# ADXL.net
KiCad netlist of a schematic drawn in EasyEDA Pro
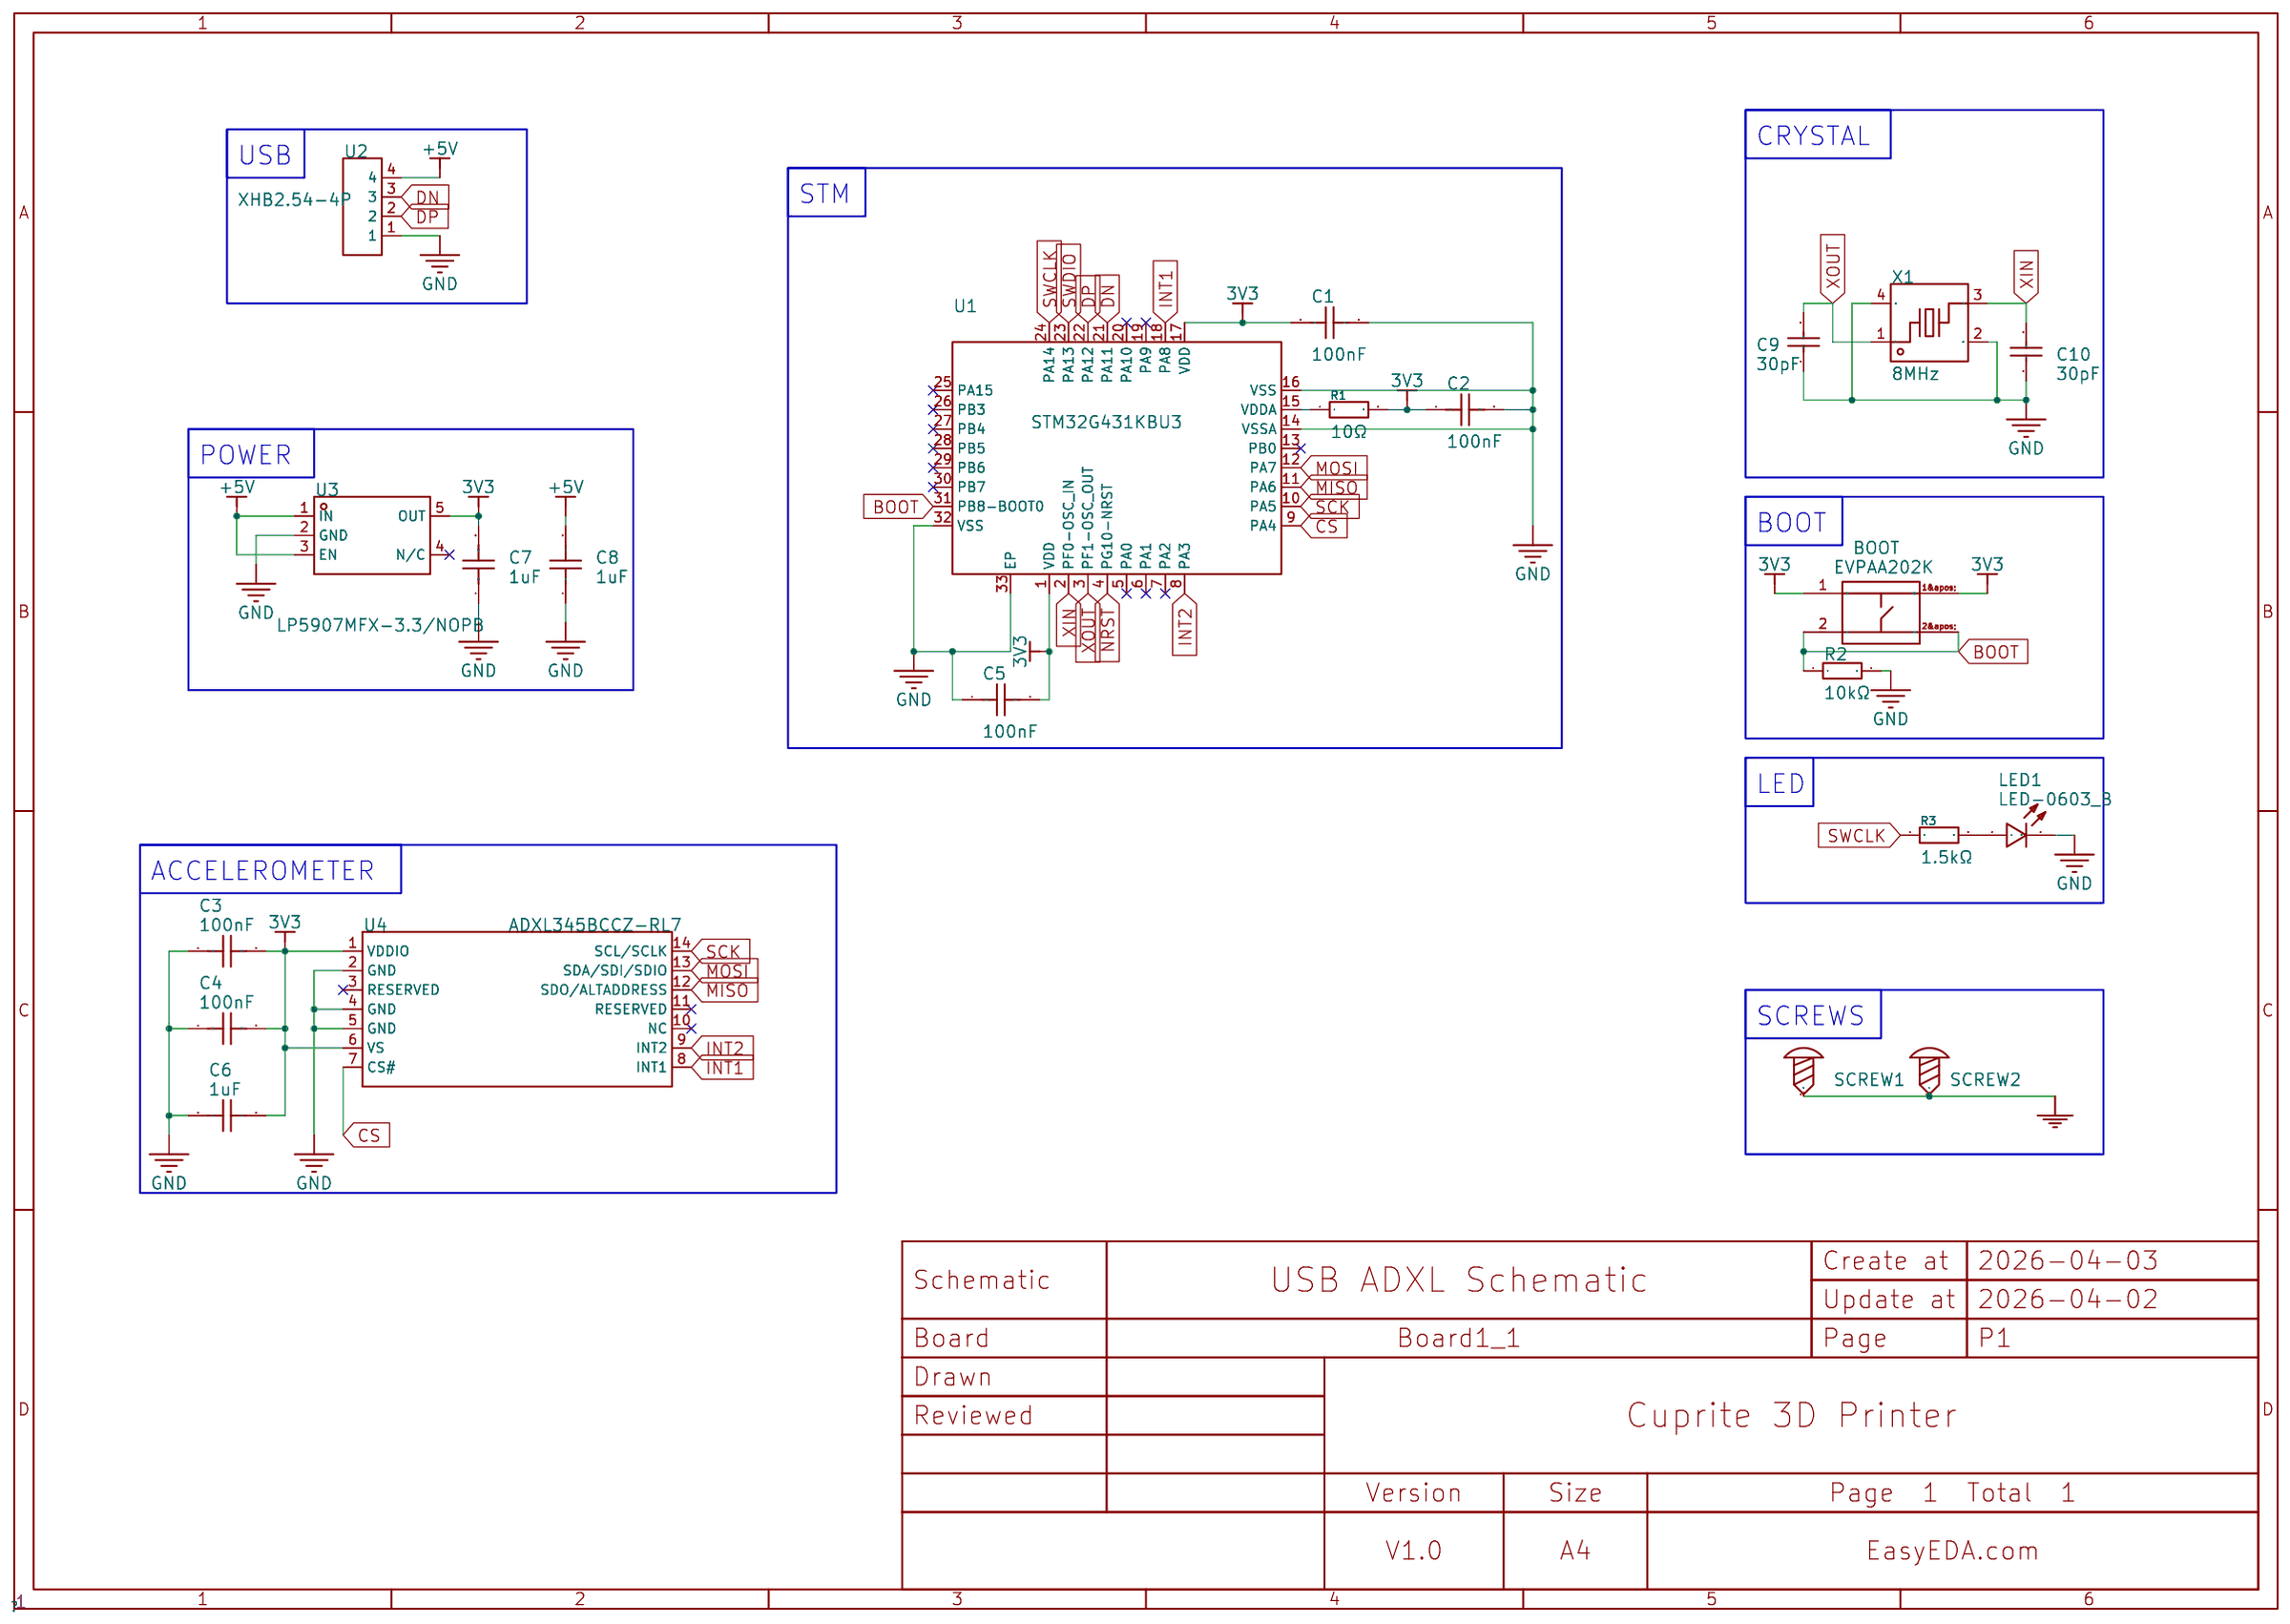
[diagram p0: schematic sheet]

(export (version "E")
  (design (tool "Eeschema 10.0.6"))
  (components
    (comp (ref "BOOT")
      (value "EVPAA202K")
      (footprint "easyedapro:KEY-SMD_4P-L3.5-W2.9-P1.48-LS4.3-TL")
      (fields (field (name "Manufacturer") "PANASONIC(松下)"))
      (libsource (lib "easyedapro") (part "EVPAA202K"))
    )
    (comp (ref "C1")
      (value "100nF")
      (footprint "easyedapro:C0402")
      (fields
        (field (name "Manufacturer Part") "CL05B104KO5NNNC")
        (field (name "Manufacturer") "SAMSUNG(三星)")
      )
      (libsource (lib "easyedapro") (part "CL05B104KO5NNNC"))
    )
    (comp (ref "C2")
      (value "100nF")
      (footprint "easyedapro:C0402")
      (fields
        (field (name "Manufacturer Part") "CL05B104KO5NNNC")
        (field (name "Manufacturer") "SAMSUNG(三星)")
      )
      (libsource (lib "easyedapro") (part "CL05B104KO5NNNC"))
    )
    (comp (ref "C3")
      (value "100nF")
      (footprint "easyedapro:C0402")
      (fields
        (field (name "Manufacturer Part") "CL05B104KO5NNNC")
        (field (name "Manufacturer") "SAMSUNG(三星)")
      )
      (libsource (lib "easyedapro") (part "CL05B104KO5NNNC"))
    )
    (comp (ref "C4")
      (value "100nF")
      (footprint "easyedapro:C0402")
      (fields
        (field (name "Manufacturer Part") "CL05B104KO5NNNC")
        (field (name "Manufacturer") "SAMSUNG(三星)")
      )
      (libsource (lib "easyedapro") (part "CL05B104KO5NNNC"))
    )
    (comp (ref "C5")
      (value "100nF")
      (footprint "easyedapro:C0402")
      (fields
        (field (name "Manufacturer Part") "CL05B104KO5NNNC")
        (field (name "Manufacturer") "SAMSUNG(三星)")
      )
      (libsource (lib "easyedapro") (part "CL05B104KO5NNNC"))
    )
    (comp (ref "C6")
      (value "1uF")
      (footprint "easyedapro:C0402")
      (fields
        (field (name "Manufacturer Part") "CL05A105KA5NQNC")
        (field (name "Manufacturer") "SAMSUNG(三星)")
      )
      (libsource (lib "easyedapro") (part "CL05A105KA5NQNC"))
    )
    (comp (ref "C7")
      (value "1uF")
      (footprint "easyedapro:C0402")
      (fields
        (field (name "Manufacturer Part") "CL05A105KA5NQNC")
        (field (name "Manufacturer") "SAMSUNG(三星)")
      )
      (libsource (lib "easyedapro") (part "CL05A105KA5NQNC"))
    )
    (comp (ref "C8")
      (value "1uF")
      (footprint "easyedapro:C0402")
      (fields
        (field (name "Manufacturer Part") "CL05A105KA5NQNC")
        (field (name "Manufacturer") "SAMSUNG(三星)")
      )
      (libsource (lib "easyedapro") (part "CL05A105KA5NQNC"))
    )
    (comp (ref "C9")
      (value "30pF")
      (footprint "easyedapro:C0402")
      (fields (field (name "Manufacturer Part") "0402CG300J500NT") (field (name "Manufacturer") "FH(风华)"))
      (libsource (lib "easyedapro") (part "0402CG300J500NT"))
    )
    (comp (ref "C10")
      (value "30pF")
      (footprint "easyedapro:C0402")
      (fields (field (name "Manufacturer Part") "0402CG300J500NT") (field (name "Manufacturer") "FH(风华)"))
      (libsource (lib "easyedapro") (part "0402CG300J500NT"))
    )
    (comp (ref "LED1")
      (value "LED-0603_B")
      (footprint "easyedapro:LED0603-FD_BLUE")
      (fields (field (name "Manufacturer") "EVERLIGHT(亿光)"))
      (libsource (lib "easyedapro") (part "19-217/BHC-ZL1M2RY/3T"))
    )
    (comp (ref "R1")
      (value "10Ω")
      (footprint "easyedapro:R0402")
      (fields
        (field (name "Manufacturer Part") "0402WGF100JTCE")
        (field (name "Manufacturer") "UNI-ROYAL(厚声)")
      )
      (libsource (lib "easyedapro") (part "0402WGF100JTCE"))
    )
    (comp (ref "R2")
      (value "10kΩ")
      (footprint "easyedapro:R0402")
      (fields
        (field (name "Manufacturer Part") "0402WGF1002TCE")
        (field (name "Manufacturer") "UNI-ROYAL(厚声)")
      )
      (libsource (lib "easyedapro") (part "0402WGF1002TCE"))
    )
    (comp (ref "R3")
      (value "1.5kΩ")
      (footprint "easyedapro:R0402")
      (fields
        (field (name "Manufacturer Part") "0402WGF1501TCE")
        (field (name "Manufacturer") "UNI-ROYAL(厚声)")
      )
      (libsource (lib "easyedapro") (part "0402WGF1501TCE"))
    )
    (comp (ref "SCREW1")
      (value "~")
      (footprint "easyedapro:Screw-Hole-M3")
      (libsource (lib "easyedapro") (part "Screw-Hole"))
    )
    (comp (ref "SCREW2")
      (value "~")
      (footprint "easyedapro:Screw-Hole-M3")
      (libsource (lib "easyedapro") (part "Screw-Hole"))
    )
    (comp (ref "U1")
      (value "STM32G431KBU3")
      (footprint "easyedapro:UFQFPN-32_L5.0-W5.0-P0.50-BL-EP3.5")
      (fields (field (name "Manufacturer") "ST(意法半导体)"))
      (libsource (lib "easyedapro") (part "STM32G431KBU3"))
    )
    (comp (ref "U2")
      (value "XHB2.54-4P")
      (footprint "easyedapro:CONN-TH_4P-P2.54-XH2.54-LI-4P")
      (libsource (lib "easyedapro") (part "XHB2.54-4P"))
    )
    (comp (ref "U3")
      (value "LP5907MFX-3.3/NOPB")
      (footprint "easyedapro:SOT-23-5_L3.0-W1.7-P0.95-LS2.8-BR")
      (fields (field (name "Manufacturer") "TI(德州仪器)"))
      (libsource (lib "easyedapro") (part "LP5907MFX-3.3/NOPB"))
    )
    (comp (ref "U4")
      (value "ADXL345BCCZ-RL7")
      (footprint "easyedapro:LGA-14_L5.0-W3.0-P0.80-BL")
      (fields (field (name "Manufacturer") "ADI(亚德诺)"))
      (libsource (lib "easyedapro") (part "ADXL345BCCZ-RL7"))
    )
    (comp (ref "X1")
      (value "8MHz")
      (footprint "easyedapro:CRYSTAL-SMD_4P-L3.2-W2.5-BL-2")
      (fields (field (name "Manufacturer Part") "3TJ480000ZYLBC") (field (name "Manufacturer") "JYJE(晶友嘉)"))
      (libsource (lib "easyedapro") (part "3TJ480000ZYLBC"))
    )
  )
  (nets
    (net (code "1") (name "+5V") (class "Default")
      (node (ref "C8") (pin "2") (pinfunction "2_2") (pintype "unspecified"))
      (node (ref "U2") (pin "4") (pinfunction "4_4") (pintype "unspecified"))
      (node (ref "U3") (pin "1") (pinfunction "IN_1") (pintype "unspecified"))
      (node (ref "U3") (pin "3") (pinfunction "EN_3") (pintype "unspecified"))
    )
    (net (code "2") (name "3V3") (class "Default")
      (node (ref "BOOT") (pin "1") (pinfunction "1_1") (pintype "unspecified"))
      (node (ref "BOOT") (pin "1&apos;") (pinfunction "1&apos;_1&apos;") (pintype "unspecified"))
      (node (ref "C1") (pin "1") (pinfunction "1_1") (pintype "unspecified"))
      (node (ref "C2") (pin "1") (pinfunction "1_1") (pintype "unspecified"))
      (node (ref "C3") (pin "2") (pinfunction "2_2") (pintype "unspecified"))
      (node (ref "C4") (pin "2") (pinfunction "2_2") (pintype "unspecified"))
      (node (ref "C5") (pin "2") (pinfunction "2_2") (pintype "unspecified"))
      (node (ref "C6") (pin "2") (pinfunction "2_2") (pintype "unspecified"))
      (node (ref "C7") (pin "2") (pinfunction "2_2") (pintype "unspecified"))
      (node (ref "R1") (pin "2") (pinfunction "2_2") (pintype "input"))
      (node (ref "U1") (pin "1") (pinfunction "VDD_1") (pintype "unspecified"))
      (node (ref "U1") (pin "17") (pinfunction "VDD_17") (pintype "unspecified"))
      (node (ref "U3") (pin "5") (pinfunction "OUT_5") (pintype "unspecified"))
      (node (ref "U4") (pin "1") (pinfunction "VDDIO_1") (pintype "unspecified"))
      (node (ref "U4") (pin "6") (pinfunction "VS_6") (pintype "unspecified"))
    )
    (net (code "3") (name "BOOT") (class "Default")
      (node (ref "BOOT") (pin "2") (pinfunction "2_2") (pintype "unspecified"))
      (node (ref "BOOT") (pin "2&apos;") (pinfunction "2&apos;_2&apos;") (pintype "unspecified"))
      (node (ref "R2") (pin "1") (pinfunction "1_1") (pintype "input"))
      (node (ref "U1") (pin "31") (pinfunction "PB8-BOOT0_31") (pintype "unspecified"))
    )
    (net (code "4") (name "CS") (class "Default")
      (node (ref "U1") (pin "9") (pinfunction "PA4_9") (pintype "unspecified"))
      (node (ref "U4") (pin "7") (pinfunction "CS#_7") (pintype "unspecified"))
    )
    (net (code "5") (name "DN") (class "Default")
      (node (ref "U1") (pin "21") (pinfunction "PA11_21") (pintype "unspecified"))
      (node (ref "U2") (pin "3") (pinfunction "3_3") (pintype "unspecified"))
    )
    (net (code "6") (name "DP") (class "Default")
      (node (ref "U1") (pin "22") (pinfunction "PA12_22") (pintype "unspecified"))
      (node (ref "U2") (pin "2") (pinfunction "2_2") (pintype "unspecified"))
    )
    (net (code "7") (name "GND") (class "Default")
      (node (ref "C1") (pin "2") (pinfunction "2_2") (pintype "unspecified"))
      (node (ref "C10") (pin "1") (pinfunction "1_1") (pintype "input"))
      (node (ref "C2") (pin "2") (pinfunction "2_2") (pintype "unspecified"))
      (node (ref "C3") (pin "1") (pinfunction "1_1") (pintype "unspecified"))
      (node (ref "C4") (pin "1") (pinfunction "1_1") (pintype "unspecified"))
      (node (ref "C5") (pin "1") (pinfunction "1_1") (pintype "unspecified"))
      (node (ref "C6") (pin "1") (pinfunction "1_1") (pintype "unspecified"))
      (node (ref "C7") (pin "1") (pinfunction "1_1") (pintype "unspecified"))
      (node (ref "C8") (pin "1") (pinfunction "1_1") (pintype "unspecified"))
      (node (ref "C9") (pin "1") (pinfunction "1_1") (pintype "input"))
      (node (ref "LED1") (pin "1") (pinfunction "C_1") (pintype "input"))
      (node (ref "R2") (pin "2") (pinfunction "2_2") (pintype "input"))
      (node (ref "SCREW1") (pin "1") (pinfunction "1_1") (pintype "input"))
      (node (ref "SCREW2") (pin "1") (pinfunction "1_1") (pintype "input"))
      (node (ref "U1") (pin "14") (pinfunction "VSSA_14") (pintype "unspecified"))
      (node (ref "U1") (pin "16") (pinfunction "VSS_16") (pintype "unspecified"))
      (node (ref "U1") (pin "32") (pinfunction "VSS_32") (pintype "unspecified"))
      (node (ref "U1") (pin "33") (pinfunction "EP_33") (pintype "unspecified"))
      (node (ref "U2") (pin "1") (pinfunction "1_1") (pintype "unspecified"))
      (node (ref "U3") (pin "2") (pinfunction "GND_2") (pintype "unspecified"))
      (node (ref "U4") (pin "2") (pinfunction "GND_2") (pintype "unspecified"))
      (node (ref "U4") (pin "4") (pinfunction "GND_4") (pintype "unspecified"))
      (node (ref "U4") (pin "5") (pinfunction "GND_5") (pintype "unspecified"))
      (node (ref "X1") (pin "2") (pinfunction "GND_2") (pintype "input"))
      (node (ref "X1") (pin "4") (pinfunction "GND_4") (pintype "input"))
    )
    (net (code "8") (name "INT1") (class "Default")
      (node (ref "U1") (pin "18") (pinfunction "PA8_18") (pintype "unspecified"))
      (node (ref "U4") (pin "8") (pinfunction "INT1_8") (pintype "unspecified"))
    )
    (net (code "9") (name "INT2") (class "Default")
      (node (ref "U1") (pin "8") (pinfunction "PA3_8") (pintype "unspecified"))
      (node (ref "U4") (pin "9") (pinfunction "INT2_9") (pintype "unspecified"))
    )
    (net (code "10") (name "MISO") (class "Default")
      (node (ref "U1") (pin "11") (pinfunction "PA6_11") (pintype "unspecified"))
      (node (ref "U4") (pin "12") (pinfunction "SDO/ALTADDRESS_12") (pintype "unspecified"))
    )
    (net (code "11") (name "MOSI") (class "Default")
      (node (ref "U1") (pin "12") (pinfunction "PA7_12") (pintype "unspecified"))
      (node (ref "U4") (pin "13") (pinfunction "SDA/SDI/SDIO_13") (pintype "unspecified"))
    )
    (net (code "12") (name "NRST") (class "Default")
      (node (ref "U1") (pin "4") (pinfunction "PG10-NRST_4") (pintype "unspecified"))
    )
    (net (code "13") (name "Net-(LED1-A)") (class "Default")
      (node (ref "LED1") (pin "2") (pinfunction "A_2") (pintype "input"))
      (node (ref "R3") (pin "2") (pinfunction "2_2") (pintype "input"))
    )
    (net (code "14") (name "Net-(U1-VDDA)") (class "Default")
      (node (ref "R1") (pin "1") (pinfunction "1_1") (pintype "input"))
      (node (ref "U1") (pin "15") (pinfunction "VDDA_15") (pintype "unspecified"))
    )
    (net (code "15") (name "SCK") (class "Default")
      (node (ref "U1") (pin "10") (pinfunction "PA5_10") (pintype "unspecified"))
      (node (ref "U4") (pin "14") (pinfunction "SCL/SCLK_14") (pintype "unspecified"))
    )
    (net (code "16") (name "SWCLK") (class "Default")
      (node (ref "R3") (pin "1") (pinfunction "1_1") (pintype "input"))
      (node (ref "U1") (pin "24") (pinfunction "PA14_24") (pintype "unspecified"))
    )
    (net (code "17") (name "SWDIO") (class "Default")
      (node (ref "U1") (pin "23") (pinfunction "PA13_23") (pintype "unspecified"))
    )
    (net (code "18") (name "XIN") (class "Default")
      (node (ref "C10") (pin "2") (pinfunction "2_2") (pintype "input"))
      (node (ref "U1") (pin "2") (pinfunction "PF0-OSC_IN_2") (pintype "unspecified"))
      (node (ref "X1") (pin "3") (pinfunction "3_3") (pintype "input"))
    )
    (net (code "19") (name "XOUT") (class "Default")
      (node (ref "C9") (pin "2") (pinfunction "2_2") (pintype "input"))
      (node (ref "U1") (pin "3") (pinfunction "PF1-OSC_OUT_3") (pintype "unspecified"))
      (node (ref "X1") (pin "1") (pinfunction "1_1") (pintype "input"))
    )
    (net (code "20") (name "unconnected-(U1-PA0-Pad5)") (class "Default")
      (node (ref "U1") (pin "5") (pinfunction "PA0_5") (pintype "unspecified+no_connect"))
    )
    (net (code "21") (name "unconnected-(U1-PA1-Pad6)") (class "Default")
      (node (ref "U1") (pin "6") (pinfunction "PA1_6") (pintype "unspecified+no_connect"))
    )
    (net (code "22") (name "unconnected-(U1-PA2-Pad7)") (class "Default")
      (node (ref "U1") (pin "7") (pinfunction "PA2_7") (pintype "unspecified+no_connect"))
    )
    (net (code "23") (name "unconnected-(U1-PA9-Pad19)") (class "Default")
      (node (ref "U1") (pin "19") (pinfunction "PA9_19") (pintype "unspecified+no_connect"))
    )
    (net (code "24") (name "unconnected-(U1-PA10-Pad20)") (class "Default")
      (node (ref "U1") (pin "20") (pinfunction "PA10_20") (pintype "unspecified+no_connect"))
    )
    (net (code "25") (name "unconnected-(U1-PA15-Pad25)") (class "Default")
      (node (ref "U1") (pin "25") (pinfunction "PA15_25") (pintype "unspecified+no_connect"))
    )
    (net (code "26") (name "unconnected-(U1-PB0-Pad13)") (class "Default")
      (node (ref "U1") (pin "13") (pinfunction "PB0_13") (pintype "unspecified+no_connect"))
    )
    (net (code "27") (name "unconnected-(U1-PB3-Pad26)") (class "Default")
      (node (ref "U1") (pin "26") (pinfunction "PB3_26") (pintype "unspecified+no_connect"))
    )
    (net (code "28") (name "unconnected-(U1-PB4-Pad27)") (class "Default")
      (node (ref "U1") (pin "27") (pinfunction "PB4_27") (pintype "unspecified+no_connect"))
    )
    (net (code "29") (name "unconnected-(U1-PB5-Pad28)") (class "Default")
      (node (ref "U1") (pin "28") (pinfunction "PB5_28") (pintype "unspecified+no_connect"))
    )
    (net (code "30") (name "unconnected-(U1-PB6-Pad29)") (class "Default")
      (node (ref "U1") (pin "29") (pinfunction "PB6_29") (pintype "unspecified+no_connect"))
    )
    (net (code "31") (name "unconnected-(U1-PB7-Pad30)") (class "Default")
      (node (ref "U1") (pin "30") (pinfunction "PB7_30") (pintype "unspecified+no_connect"))
    )
    (net (code "32") (name "unconnected-(U3-N{slash}C-Pad4)") (class "Default")
      (node (ref "U3") (pin "4") (pinfunction "N/C_4") (pintype "unspecified+no_connect"))
    )
    (net (code "33") (name "unconnected-(U4-NC-Pad10)") (class "Default")
      (node (ref "U4") (pin "10") (pinfunction "NC_10") (pintype "unspecified+no_connect"))
    )
    (net (code "34") (name "unconnected-(U4-RESERVED-Pad3)") (class "Default")
      (node (ref "U4") (pin "3") (pinfunction "RESERVED_3") (pintype "unspecified+no_connect"))
    )
    (net (code "35") (name "unconnected-(U4-RESERVED-Pad11)") (class "Default")
      (node (ref "U4") (pin "11") (pinfunction "RESERVED_11") (pintype "unspecified+no_connect"))
    )
  )
)
